# modEEGdigital_v1_1.net
KiCad netlist of a schematic drawn in EAGLE
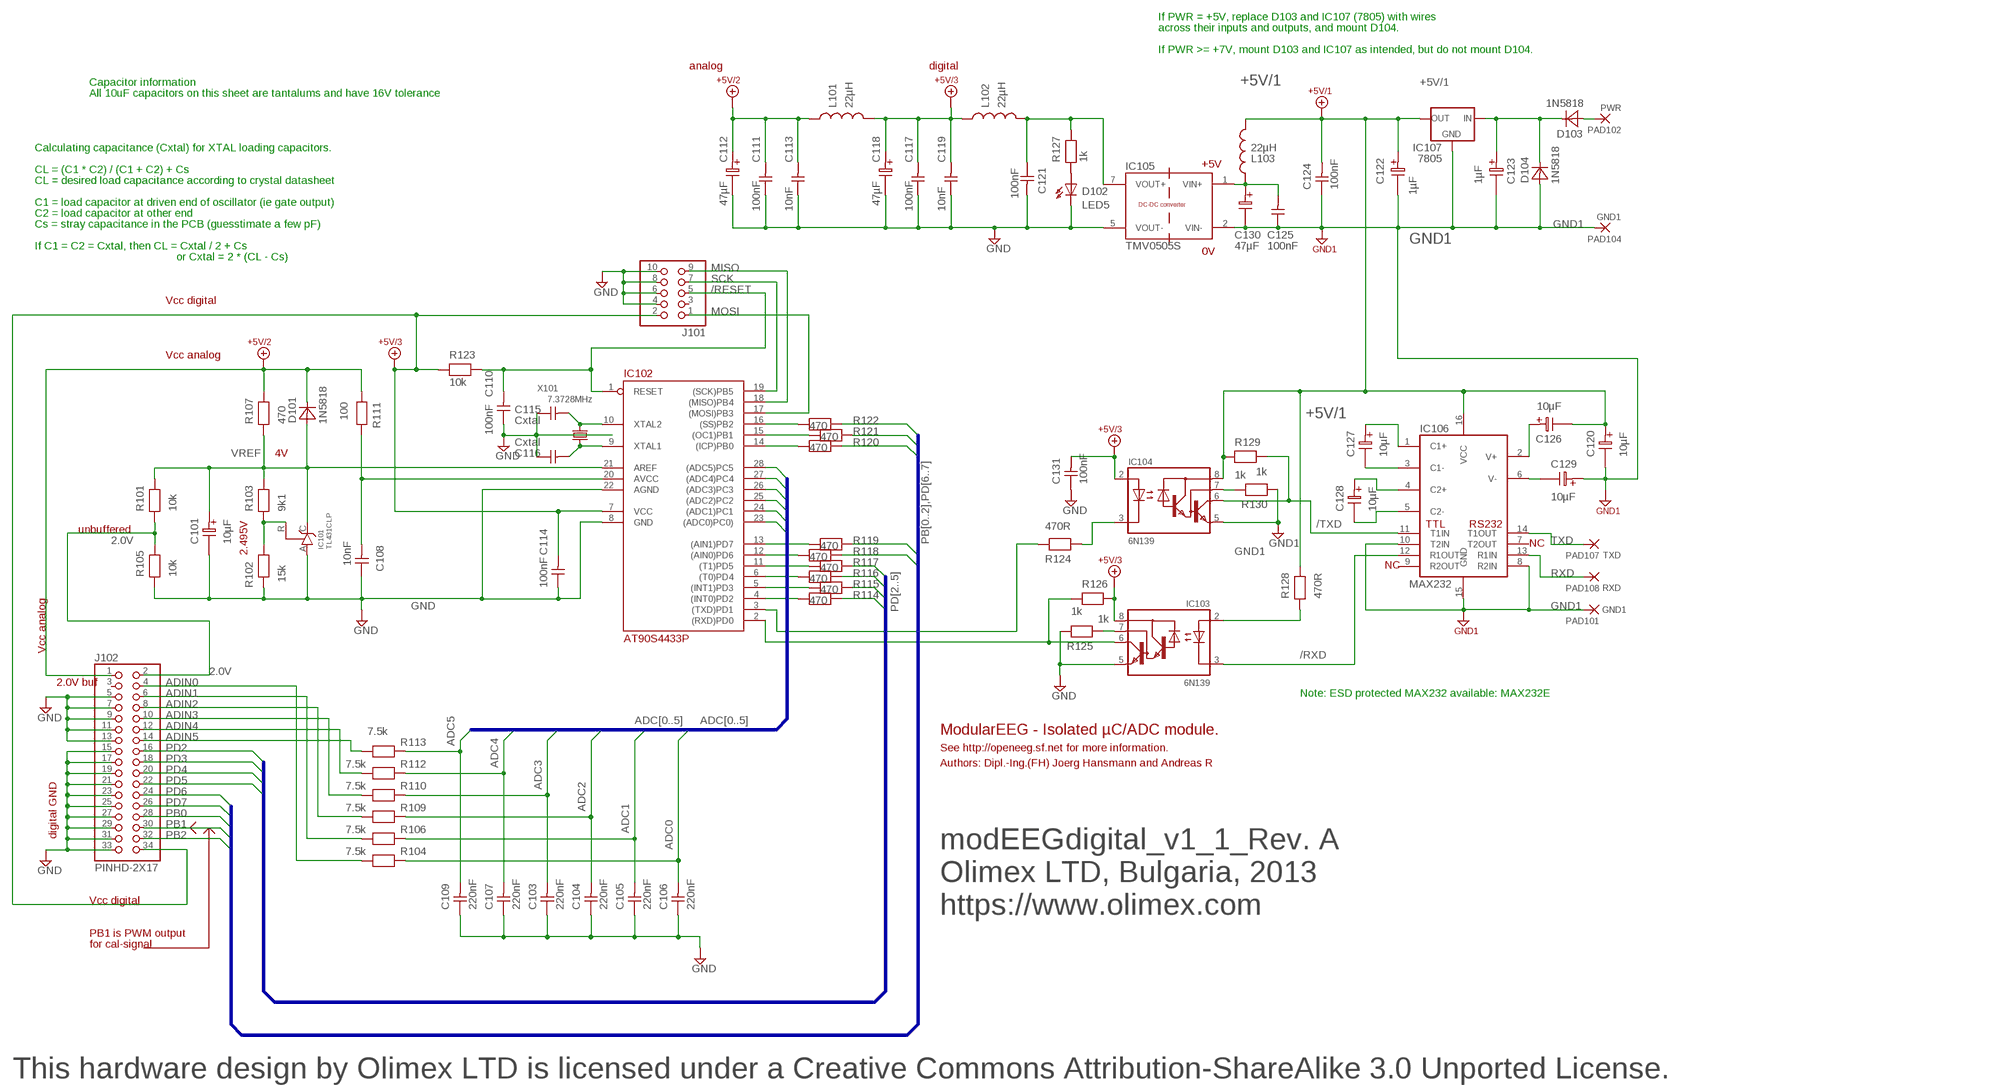
[diagram p0: schematic, sheet 1]

(export (version "E")
  (design (tool "Eeschema 10.0.6"))
  (components
    (comp (ref "C101")
      (value "10µF")
      (footprint "eagle-import:EL25B")
      (libsource (lib "eagle-import") (part "ELC-5"))
    )
    (comp (ref "C103")
      (value "220nF")
      (footprint "eagle-import:C-5")
      (libsource (lib "eagle-import") (part "CAPNP-5"))
    )
    (comp (ref "C104")
      (value "220nF")
      (footprint "eagle-import:C-5")
      (libsource (lib "eagle-import") (part "CAPNP-5"))
    )
    (comp (ref "C105")
      (value "220nF")
      (footprint "eagle-import:C-5")
      (libsource (lib "eagle-import") (part "CAPNP-5"))
    )
    (comp (ref "C106")
      (value "220nF")
      (footprint "eagle-import:C-5")
      (libsource (lib "eagle-import") (part "CAPNP-5"))
    )
    (comp (ref "C107")
      (value "220nF")
      (footprint "eagle-import:C-5")
      (libsource (lib "eagle-import") (part "CAPNP-5"))
    )
    (comp (ref "C108")
      (value "10nF")
      (footprint "eagle-import:C-5")
      (libsource (lib "eagle-import") (part "CAPNP-5"))
    )
    (comp (ref "C109")
      (value "220nF")
      (footprint "eagle-import:C-5")
      (libsource (lib "eagle-import") (part "CAPNP-5"))
    )
    (comp (ref "C110")
      (value "100nF")
      (footprint "eagle-import:C-5")
      (libsource (lib "eagle-import") (part "CAPNP-5"))
    )
    (comp (ref "C111")
      (value "100nF")
      (footprint "eagle-import:C-5")
      (libsource (lib "eagle-import") (part "CAPNP-5"))
    )
    (comp (ref "C112")
      (value "47µF")
      (footprint "eagle-import:EL25B")
      (libsource (lib "eagle-import") (part "ELC-5"))
    )
    (comp (ref "C113")
      (value "10nF")
      (footprint "eagle-import:C-5")
      (libsource (lib "eagle-import") (part "CAPNP-5"))
    )
    (comp (ref "C114")
      (value "100nF")
      (footprint "eagle-import:C-5")
      (libsource (lib "eagle-import") (part "CAPNP-5"))
    )
    (comp (ref "C115")
      (value "Cxtal")
      (footprint "eagle-import:C-5")
      (libsource (lib "eagle-import") (part "CAPNP-5"))
    )
    (comp (ref "C116")
      (value "Cxtal")
      (footprint "eagle-import:C-5")
      (libsource (lib "eagle-import") (part "CAPNP-5"))
    )
    (comp (ref "C117")
      (value "100nF")
      (footprint "eagle-import:C-5")
      (libsource (lib "eagle-import") (part "CAPNP-5"))
    )
    (comp (ref "C118")
      (value "47µF")
      (footprint "eagle-import:EL25B")
      (libsource (lib "eagle-import") (part "ELC-5"))
    )
    (comp (ref "C119")
      (value "10nF")
      (footprint "eagle-import:C-5")
      (libsource (lib "eagle-import") (part "CAPNP-5"))
    )
    (comp (ref "C120")
      (value "10µF")
      (footprint "eagle-import:EL25B")
      (libsource (lib "eagle-import") (part "ELC-5"))
    )
    (comp (ref "C121")
      (value "100nF")
      (footprint "eagle-import:C-5@1")
      (libsource (lib "eagle-import") (part "CAPNP-5@2"))
    )
    (comp (ref "C122")
      (value "1µF")
      (footprint "eagle-import:EL25B")
      (libsource (lib "eagle-import") (part "ELC-2,5"))
    )
    (comp (ref "C123")
      (value "1µF")
      (footprint "eagle-import:EL25B")
      (libsource (lib "eagle-import") (part "ELC-2,5"))
    )
    (comp (ref "C124")
      (value "100nF")
      (footprint "eagle-import:C-5@1")
      (libsource (lib "eagle-import") (part "CAPNP-5@2"))
    )
    (comp (ref "C125")
      (value "100nF")
      (footprint "eagle-import:C-5")
      (libsource (lib "eagle-import") (part "CAPNP-5"))
    )
    (comp (ref "C126")
      (value "10µF")
      (footprint "eagle-import:EL25B")
      (libsource (lib "eagle-import") (part "ELC-5"))
    )
    (comp (ref "C127")
      (value "10µF")
      (footprint "eagle-import:EL25B")
      (libsource (lib "eagle-import") (part "ELC-5"))
    )
    (comp (ref "C128")
      (value "10µF")
      (footprint "eagle-import:EL25B")
      (libsource (lib "eagle-import") (part "ELC-5"))
    )
    (comp (ref "C129")
      (value "10µF")
      (footprint "eagle-import:EL25B")
      (libsource (lib "eagle-import") (part "ELC-5"))
    )
    (comp (ref "C130")
      (value "47µF")
      (footprint "eagle-import:EL25B")
      (libsource (lib "eagle-import") (part "ELC-5"))
    )
    (comp (ref "C131")
      (value "100nF")
      (footprint "eagle-import:C-5")
      (libsource (lib "eagle-import") (part "CAPNP-5"))
    )
    (comp (ref "D101")
      (value "1N5818")
      (footprint "eagle-import:D-10")
      (libsource (lib "eagle-import") (part "DIODE-10"))
    )
    (comp (ref "D102")
      (value "LED5")
      (footprint "eagle-import:LED5")
      (libsource (lib "eagle-import") (part "LED5"))
    )
    (comp (ref "D103")
      (value "1N5818")
      (footprint "eagle-import:D-12,5")
      (libsource (lib "eagle-import") (part "DIODE-12,5"))
    )
    (comp (ref "D104")
      (value "1N5818")
      (footprint "eagle-import:D-12,5")
      (libsource (lib "eagle-import") (part "DIODE-12,5"))
    )
    (comp (ref "IC101")
      (value "TL431CLP")
      (footprint "eagle-import:TO92-CLP")
      (libsource (lib "eagle-import") (part "TL431CLP"))
    )
    (comp (ref "IC102")
      (value "AT90S4433P")
      (footprint "eagle-import:DIL-28_3")
      (libsource (lib "eagle-import") (part "90S4433-P"))
    )
    (comp (ref "IC103")
      (value "6N139")
      (footprint "eagle-import:DIL-08")
      (libsource (lib "eagle-import") (part "HCPL0700"))
    )
    (comp (ref "IC104")
      (value "6N139")
      (footprint "eagle-import:DIL-08")
      (libsource (lib "eagle-import") (part "HCPL0700"))
    )
    (comp (ref "IC105")
      (value "TMV0505S")
      (footprint "eagle-import:TMADCDC")
      (libsource (lib "eagle-import") (part "TMV0505"))
    )
    (comp (ref "IC106")
      (value "MAX232")
      (footprint "eagle-import:DIL-16")
      (libsource (lib "eagle-import") (part "MAX232"))
    )
    (comp (ref "IC107")
      (value "7805")
      (footprint "eagle-import:78XXL_S")
      (libsource (lib "eagle-import") (part "78XXS"))
    )
    (comp (ref "J101")
      (value "PINHD-2X5")
      (footprint "eagle-import:2X05")
      (libsource (lib "eagle-import") (part "PINHD-2X5"))
    )
    (comp (ref "J102")
      (value "PINHD-2X17")
      (footprint "eagle-import:2X17")
      (libsource (lib "eagle-import") (part "PINHD-2X17"))
    )
    (comp (ref "L101")
      (value "22µH")
      (footprint "eagle-import:R-12,5")
      (libsource (lib "eagle-import") (part "L-10"))
    )
    (comp (ref "L102")
      (value "22µH")
      (footprint "eagle-import:R-12,5")
      (libsource (lib "eagle-import") (part "L-10"))
    )
    (comp (ref "L103")
      (value "22µH")
      (footprint "eagle-import:R-12,5")
      (libsource (lib "eagle-import") (part "L-10"))
    )
    (comp (ref "PAD101")
      (value "GND1")
      (footprint "eagle-import:WIREPAD1")
      (libsource (lib "eagle-import") (part "1,6/0,8"))
    )
    (comp (ref "PAD102")
      (value "PWR")
      (footprint "eagle-import:WIREPAD1")
      (libsource (lib "eagle-import") (part "1,6/0,8"))
    )
    (comp (ref "PAD104")
      (value "GND1")
      (footprint "eagle-import:WIREPAD1")
      (libsource (lib "eagle-import") (part "1,6/0,8"))
    )
    (comp (ref "PAD107")
      (value "TXD")
      (footprint "eagle-import:WIREPAD1")
      (libsource (lib "eagle-import") (part "1,6/0,8"))
    )
    (comp (ref "PAD108")
      (value "RXD")
      (footprint "eagle-import:WIREPAD1")
      (libsource (lib "eagle-import") (part "1,6/0,8"))
    )
    (comp (ref "R101")
      (value "10k")
      (footprint "eagle-import:R-10")
      (libsource (lib "eagle-import") (part "RESEU-10"))
    )
    (comp (ref "R102")
      (value "15k")
      (footprint "eagle-import:R-10")
      (libsource (lib "eagle-import") (part "RESEU-10"))
    )
    (comp (ref "R103")
      (value "9k1")
      (footprint "eagle-import:R-10")
      (libsource (lib "eagle-import") (part "RESEU-10"))
    )
    (comp (ref "R104")
      (value "7.5k")
      (footprint "eagle-import:R-10")
      (libsource (lib "eagle-import") (part "RESEU-10"))
    )
    (comp (ref "R105")
      (value "10k")
      (footprint "eagle-import:R-10")
      (libsource (lib "eagle-import") (part "RESEU-10"))
    )
    (comp (ref "R106")
      (value "7.5k")
      (footprint "eagle-import:R-10")
      (libsource (lib "eagle-import") (part "RESEU-10"))
    )
    (comp (ref "R107")
      (value "470")
      (footprint "eagle-import:R-10")
      (libsource (lib "eagle-import") (part "RESEU-10"))
    )
    (comp (ref "R109")
      (value "7.5k")
      (footprint "eagle-import:R-10")
      (libsource (lib "eagle-import") (part "RESEU-10"))
    )
    (comp (ref "R110")
      (value "7.5k")
      (footprint "eagle-import:R-10")
      (libsource (lib "eagle-import") (part "RESEU-10"))
    )
    (comp (ref "R111")
      (value "100")
      (footprint "eagle-import:R-10")
      (libsource (lib "eagle-import") (part "RESEU-10"))
    )
    (comp (ref "R112")
      (value "7.5k")
      (footprint "eagle-import:R-10")
      (libsource (lib "eagle-import") (part "RESEU-10"))
    )
    (comp (ref "R113")
      (value "7.5k")
      (footprint "eagle-import:R-10")
      (libsource (lib "eagle-import") (part "RESEU-10"))
    )
    (comp (ref "R114")
      (value "470")
      (footprint "eagle-import:R-10")
      (libsource (lib "eagle-import") (part "RESEU-10"))
    )
    (comp (ref "R115")
      (value "470")
      (footprint "eagle-import:R-10")
      (libsource (lib "eagle-import") (part "RESEU-10"))
    )
    (comp (ref "R116")
      (value "470")
      (footprint "eagle-import:R-10")
      (libsource (lib "eagle-import") (part "RESEU-10"))
    )
    (comp (ref "R117")
      (value "470")
      (footprint "eagle-import:R-10")
      (libsource (lib "eagle-import") (part "RESEU-10"))
    )
    (comp (ref "R118")
      (value "470")
      (footprint "eagle-import:R-10")
      (libsource (lib "eagle-import") (part "RESEU-10"))
    )
    (comp (ref "R119")
      (value "470")
      (footprint "eagle-import:R-10")
      (libsource (lib "eagle-import") (part "RESEU-10"))
    )
    (comp (ref "R120")
      (value "470")
      (footprint "eagle-import:R-10")
      (libsource (lib "eagle-import") (part "RESEU-10"))
    )
    (comp (ref "R121")
      (value "470")
      (footprint "eagle-import:R-10")
      (libsource (lib "eagle-import") (part "RESEU-10"))
    )
    (comp (ref "R122")
      (value "470")
      (footprint "eagle-import:R-10")
      (libsource (lib "eagle-import") (part "RESEU-10"))
    )
    (comp (ref "R123")
      (value "10k")
      (footprint "eagle-import:R-10")
      (libsource (lib "eagle-import") (part "RESEU-10@2"))
    )
    (comp (ref "R124")
      (value "470R")
      (footprint "eagle-import:R-10")
      (libsource (lib "eagle-import") (part "RESEU-10"))
    )
    (comp (ref "R125")
      (value "1k")
      (footprint "eagle-import:R-10")
      (libsource (lib "eagle-import") (part "RESEU-10"))
    )
    (comp (ref "R126")
      (value "1k")
      (footprint "eagle-import:R-10")
      (libsource (lib "eagle-import") (part "RESEU-10"))
    )
    (comp (ref "R127")
      (value "1k")
      (footprint "eagle-import:R-10")
      (libsource (lib "eagle-import") (part "RESEU-10@2"))
    )
    (comp (ref "R128")
      (value "470R")
      (footprint "eagle-import:R-10")
      (libsource (lib "eagle-import") (part "RESEU-10"))
    )
    (comp (ref "R129")
      (value "1k")
      (footprint "eagle-import:R-10")
      (libsource (lib "eagle-import") (part "RESEU-10"))
    )
    (comp (ref "R130")
      (value "1k")
      (footprint "eagle-import:R-10")
      (libsource (lib "eagle-import") (part "RESEU-10"))
    )
    (comp (ref "X101")
      (value "7.3728MHz")
      (footprint "eagle-import:HC49_S")
      (libsource (lib "eagle-import") (part "HC49/S"))
    )
  )
  (nets
    (net (code "1") (name "+5V{slash}1") (class "Default")
      (node (ref "C120") (pin "1") (pinfunction "1_1") (pintype "passive"))
      (node (ref "C122") (pin "1") (pinfunction "1_1") (pintype "passive"))
      (node (ref "C124") (pin "2") (pinfunction "2_2") (pintype "passive"))
      (node (ref "C126") (pin "2") (pinfunction "2_2") (pintype "passive"))
      (node (ref "IC104") (pin "8") (pinfunction "VCC_8") (pintype "passive"))
      (node (ref "IC106") (pin "16") (pinfunction "VCC_16") (pintype "power_in"))
      (node (ref "IC107") (pin "OUT") (pinfunction "OUT_OUT") (pintype "passive"))
      (node (ref "L103") (pin "2") (pinfunction "2_2") (pintype "passive"))
      (node (ref "R128") (pin "2") (pinfunction "2_2") (pintype "passive"))
      (node (ref "R129") (pin "1") (pinfunction "1_1") (pintype "passive"))
    )
    (net (code "2") (name "+5V{slash}2") (class "Default")
      (node (ref "C111") (pin "2") (pinfunction "2_2") (pintype "passive"))
      (node (ref "C112") (pin "1") (pinfunction "1_1") (pintype "passive"))
      (node (ref "C113") (pin "2") (pinfunction "2_2") (pintype "passive"))
      (node (ref "D101") (pin "2") (pinfunction "K_2") (pintype "passive"))
      (node (ref "J102") (pin "1") (pinfunction "1_1") (pintype "passive"))
      (node (ref "L101") (pin "1") (pinfunction "1_1") (pintype "passive"))
      (node (ref "R107") (pin "2") (pinfunction "2_2") (pintype "passive"))
      (node (ref "R111") (pin "1") (pinfunction "1_1") (pintype "passive"))
    )
    (net (code "3") (name "+5V{slash}3") (class "Default")
      (node (ref "C114") (pin "2") (pinfunction "2_2") (pintype "passive"))
      (node (ref "C117") (pin "2") (pinfunction "2_2") (pintype "passive"))
      (node (ref "C118") (pin "1") (pinfunction "1_1") (pintype "passive"))
      (node (ref "C119") (pin "2") (pinfunction "2_2") (pintype "passive"))
      (node (ref "C131") (pin "2") (pinfunction "2_2") (pintype "passive"))
      (node (ref "IC102") (pin "7") (pinfunction "VCC_7") (pintype "power_in"))
      (node (ref "IC103") (pin "8") (pinfunction "VCC_8") (pintype "passive"))
      (node (ref "IC104") (pin "2") (pinfunction "A_2") (pintype "passive"))
      (node (ref "J101") (pin "2") (pinfunction "2_2") (pintype "passive"))
      (node (ref "J102") (pin "34") (pinfunction "34_34") (pintype "passive"))
      (node (ref "L101") (pin "2") (pinfunction "2_2") (pintype "passive"))
      (node (ref "L102") (pin "1") (pinfunction "1_1") (pintype "passive"))
      (node (ref "R123") (pin "1") (pinfunction "1_1") (pintype "passive"))
      (node (ref "R126") (pin "2") (pinfunction "2_2") (pintype "passive"))
    )
    (net (code "4") (name "/2.0V") (class "Default")
      (node (ref "J102") (pin "2") (pinfunction "2_2") (pintype "passive"))
      (node (ref "R101") (pin "1") (pinfunction "1_1") (pintype "passive"))
      (node (ref "R105") (pin "2") (pinfunction "2_2") (pintype "passive"))
    )
    (net (code "5") (name "/ADC0") (class "Default")
      (node (ref "C106") (pin "2") (pinfunction "2_2") (pintype "passive"))
      (node (ref "IC102") (pin "23") (pinfunction "(ADC0)PC0)_23") (pintype "bidirectional"))
      (node (ref "R104") (pin "2") (pinfunction "2_2") (pintype "passive"))
    )
    (net (code "6") (name "/ADC1") (class "Default")
      (node (ref "C105") (pin "2") (pinfunction "2_2") (pintype "passive"))
      (node (ref "IC102") (pin "24") (pinfunction "(ADC1)PC1_24") (pintype "bidirectional"))
      (node (ref "R106") (pin "2") (pinfunction "2_2") (pintype "passive"))
    )
    (net (code "7") (name "/ADC2") (class "Default")
      (node (ref "C104") (pin "2") (pinfunction "2_2") (pintype "passive"))
      (node (ref "IC102") (pin "25") (pinfunction "(ADC2)PC2_25") (pintype "bidirectional"))
      (node (ref "R109") (pin "2") (pinfunction "2_2") (pintype "passive"))
    )
    (net (code "8") (name "/ADC3") (class "Default")
      (node (ref "C103") (pin "2") (pinfunction "2_2") (pintype "passive"))
      (node (ref "IC102") (pin "26") (pinfunction "(ADC3)PC3_26") (pintype "bidirectional"))
      (node (ref "R110") (pin "2") (pinfunction "2_2") (pintype "passive"))
    )
    (net (code "9") (name "/ADC4") (class "Default")
      (node (ref "C107") (pin "2") (pinfunction "2_2") (pintype "passive"))
      (node (ref "IC102") (pin "27") (pinfunction "(ADC4)PC4_27") (pintype "bidirectional"))
      (node (ref "R112") (pin "2") (pinfunction "2_2") (pintype "passive"))
    )
    (net (code "10") (name "/ADC5") (class "Default")
      (node (ref "C109") (pin "2") (pinfunction "2_2") (pintype "passive"))
      (node (ref "IC102") (pin "28") (pinfunction "(ADC5)PC5_28") (pintype "bidirectional"))
      (node (ref "R113") (pin "2") (pinfunction "2_2") (pintype "passive"))
    )
    (net (code "12") (name "/ADIN0") (class "Default")
      (node (ref "J102") (pin "4") (pinfunction "4_4") (pintype "passive"))
      (node (ref "R104") (pin "1") (pinfunction "1_1") (pintype "passive"))
    )
    (net (code "13") (name "/ADIN1") (class "Default")
      (node (ref "J102") (pin "6") (pinfunction "6_6") (pintype "passive"))
      (node (ref "R106") (pin "1") (pinfunction "1_1") (pintype "passive"))
    )
    (net (code "14") (name "/ADIN2") (class "Default")
      (node (ref "J102") (pin "8") (pinfunction "8_8") (pintype "passive"))
      (node (ref "R109") (pin "1") (pinfunction "1_1") (pintype "passive"))
    )
    (net (code "15") (name "/ADIN3") (class "Default")
      (node (ref "J102") (pin "10") (pinfunction "10_10") (pintype "passive"))
      (node (ref "R110") (pin "1") (pinfunction "1_1") (pintype "passive"))
    )
    (net (code "16") (name "/ADIN4") (class "Default")
      (node (ref "J102") (pin "12") (pinfunction "12_12") (pintype "passive"))
      (node (ref "R112") (pin "1") (pinfunction "1_1") (pintype "passive"))
    )
    (net (code "17") (name "/ADIN5") (class "Default")
      (node (ref "J102") (pin "14") (pinfunction "14_14") (pintype "passive"))
      (node (ref "R113") (pin "1") (pinfunction "1_1") (pintype "passive"))
    )
    (net (code "18") (name "/MISO") (class "Default")
      (node (ref "IC102") (pin "18") (pinfunction "(MISO)PB4_18") (pintype "bidirectional"))
      (node (ref "J101") (pin "9") (pinfunction "9_9") (pintype "passive"))
    )
    (net (code "19") (name "/MOSI") (class "Default")
      (node (ref "IC102") (pin "17") (pinfunction "(MOSI)PB3_17") (pintype "bidirectional"))
      (node (ref "J101") (pin "1") (pinfunction "1_1") (pintype "passive"))
    )
    (net (code "20") (name "/PB0") (class "Default")
      (node (ref "J102") (pin "28") (pinfunction "28_28") (pintype "passive"))
      (node (ref "R120") (pin "2") (pinfunction "2_2") (pintype "passive"))
    )
    (net (code "21") (name "/PB1") (class "Default")
      (node (ref "J102") (pin "30") (pinfunction "30_30") (pintype "passive"))
      (node (ref "R121") (pin "2") (pinfunction "2_2") (pintype "passive"))
    )
    (net (code "22") (name "/PB2") (class "Default")
      (node (ref "J102") (pin "32") (pinfunction "32_32") (pintype "passive"))
      (node (ref "R122") (pin "2") (pinfunction "2_2") (pintype "passive"))
    )
    (net (code "23") (name "/PD2") (class "Default")
      (node (ref "J102") (pin "16") (pinfunction "16_16") (pintype "passive"))
      (node (ref "R114") (pin "2") (pinfunction "2_2") (pintype "passive"))
    )
    (net (code "24") (name "/PD3") (class "Default")
      (node (ref "J102") (pin "18") (pinfunction "18_18") (pintype "passive"))
      (node (ref "R115") (pin "2") (pinfunction "2_2") (pintype "passive"))
    )
    (net (code "25") (name "/PD4") (class "Default")
      (node (ref "J102") (pin "20") (pinfunction "20_20") (pintype "passive"))
      (node (ref "R116") (pin "2") (pinfunction "2_2") (pintype "passive"))
    )
    (net (code "26") (name "/PD5") (class "Default")
      (node (ref "J102") (pin "22") (pinfunction "22_22") (pintype "passive"))
      (node (ref "R117") (pin "2") (pinfunction "2_2") (pintype "passive"))
    )
    (net (code "27") (name "/PD6") (class "Default")
      (node (ref "J102") (pin "24") (pinfunction "24_24") (pintype "passive"))
      (node (ref "R118") (pin "2") (pinfunction "2_2") (pintype "passive"))
    )
    (net (code "28") (name "/PD7") (class "Default")
      (node (ref "J102") (pin "26") (pinfunction "26_26") (pintype "passive"))
      (node (ref "R119") (pin "2") (pinfunction "2_2") (pintype "passive"))
    )
    (net (code "29") (name "/RXD") (class "Default")
      (node (ref "IC106") (pin "13") (pinfunction "R1IN_13") (pintype "input"))
      (node (ref "PAD108") (pin "1") (pinfunction "P_1") (pintype "passive"))
    )
    (net (code "30") (name "/SCK") (class "Default")
      (node (ref "IC102") (pin "19") (pinfunction "(SCK)PB5_19") (pintype "bidirectional"))
      (node (ref "J101") (pin "7") (pinfunction "7_7") (pintype "passive"))
    )
    (net (code "31") (name "/TXD") (class "Default")
      (node (ref "IC106") (pin "14") (pinfunction "T1OUT_14") (pintype "output"))
      (node (ref "PAD107") (pin "1") (pinfunction "P_1") (pintype "passive"))
    )
    (net (code "32") (name "/VREF") (class "Default")
      (node (ref "C101") (pin "1") (pinfunction "1_1") (pintype "passive"))
      (node (ref "D101") (pin "1") (pinfunction "A_1") (pintype "passive"))
      (node (ref "IC101") (pin "C") (pinfunction "C_C") (pintype "passive"))
      (node (ref "IC102") (pin "21") (pinfunction "AREF_21") (pintype "power_in"))
      (node (ref "R101") (pin "2") (pinfunction "2_2") (pintype "passive"))
      (node (ref "R103") (pin "2") (pinfunction "2_2") (pintype "passive"))
      (node (ref "R107") (pin "1") (pinfunction "1_1") (pintype "passive"))
    )
    (net (code "34") (name "/{slash}RESET") (class "Default")
      (node (ref "C110") (pin "2") (pinfunction "2_2") (pintype "passive"))
      (node (ref "IC102") (pin "1") (pinfunction "RESET_1") (pintype "input"))
      (node (ref "J101") (pin "5") (pinfunction "5_5") (pintype "passive"))
      (node (ref "R123") (pin "2") (pinfunction "2_2") (pintype "passive"))
    )
    (net (code "35") (name "/{slash}RXD") (class "Default")
      (node (ref "IC103") (pin "3") (pinfunction "K_3") (pintype "passive"))
      (node (ref "IC106") (pin "12") (pinfunction "R1OUT_12") (pintype "output"))
    )
    (net (code "36") (name "/{slash}TXD") (class "Default")
      (node (ref "IC104") (pin "6") (pinfunction "VO_6") (pintype "passive"))
      (node (ref "IC106") (pin "11") (pinfunction "T1IN_11") (pintype "input"))
      (node (ref "R129") (pin "2") (pinfunction "2_2") (pintype "passive"))
    )
    (net (code "37") (name "GND") (class "Default")
      (node (ref "C101") (pin "2") (pinfunction "2_2") (pintype "passive"))
      (node (ref "C103") (pin "1") (pinfunction "1_1") (pintype "passive"))
      (node (ref "C104") (pin "1") (pinfunction "1_1") (pintype "passive"))
      (node (ref "C105") (pin "1") (pinfunction "1_1") (pintype "passive"))
      (node (ref "C106") (pin "1") (pinfunction "1_1") (pintype "passive"))
      (node (ref "C107") (pin "1") (pinfunction "1_1") (pintype "passive"))
      (node (ref "C108") (pin "1") (pinfunction "1_1") (pintype "passive"))
      (node (ref "C109") (pin "1") (pinfunction "1_1") (pintype "passive"))
      (node (ref "C110") (pin "1") (pinfunction "1_1") (pintype "passive"))
      (node (ref "C111") (pin "1") (pinfunction "1_1") (pintype "passive"))
      (node (ref "C112") (pin "2") (pinfunction "2_2") (pintype "passive"))
      (node (ref "C113") (pin "1") (pinfunction "1_1") (pintype "passive"))
      (node (ref "C114") (pin "1") (pinfunction "1_1") (pintype "passive"))
      (node (ref "C115") (pin "1") (pinfunction "1_1") (pintype "passive"))
      (node (ref "C116") (pin "1") (pinfunction "1_1") (pintype "passive"))
      (node (ref "C117") (pin "1") (pinfunction "1_1") (pintype "passive"))
      (node (ref "C118") (pin "2") (pinfunction "2_2") (pintype "passive"))
      (node (ref "C119") (pin "1") (pinfunction "1_1") (pintype "passive"))
      (node (ref "C121") (pin "2") (pinfunction "2_2") (pintype "passive"))
      (node (ref "C131") (pin "1") (pinfunction "1_1") (pintype "passive"))
      (node (ref "D102") (pin "K") (pinfunction "K_K") (pintype "passive"))
      (node (ref "IC101") (pin "A") (pinfunction "A_A") (pintype "passive"))
      (node (ref "IC102") (pin "22") (pinfunction "AGND_22") (pintype "power_in"))
      (node (ref "IC102") (pin "8") (pinfunction "GND_8") (pintype "power_in"))
      (node (ref "IC103") (pin "5") (pinfunction "GND_5") (pintype "passive"))
      (node (ref "IC105") (pin "5") (pinfunction "VOUT-_5") (pintype "power_in"))
      (node (ref "J101") (pin "10") (pinfunction "10_10") (pintype "passive"))
      (node (ref "J101") (pin "4") (pinfunction "4_4") (pintype "passive"))
      (node (ref "J101") (pin "6") (pinfunction "6_6") (pintype "passive"))
      (node (ref "J101") (pin "8") (pinfunction "8_8") (pintype "passive"))
      (node (ref "J102") (pin "11") (pinfunction "11_11") (pintype "passive"))
      (node (ref "J102") (pin "13") (pinfunction "13_13") (pintype "passive"))
      (node (ref "J102") (pin "15") (pinfunction "15_15") (pintype "passive"))
      (node (ref "J102") (pin "17") (pinfunction "17_17") (pintype "passive"))
      (node (ref "J102") (pin "19") (pinfunction "19_19") (pintype "passive"))
      (node (ref "J102") (pin "21") (pinfunction "21_21") (pintype "passive"))
      (node (ref "J102") (pin "23") (pinfunction "23_23") (pintype "passive"))
      (node (ref "J102") (pin "25") (pinfunction "25_25") (pintype "passive"))
      (node (ref "J102") (pin "27") (pinfunction "27_27") (pintype "passive"))
      (node (ref "J102") (pin "29") (pinfunction "29_29") (pintype "passive"))
      (node (ref "J102") (pin "31") (pinfunction "31_31") (pintype "passive"))
      (node (ref "J102") (pin "33") (pinfunction "33_33") (pintype "passive"))
      (node (ref "J102") (pin "5") (pinfunction "5_5") (pintype "passive"))
      (node (ref "J102") (pin "7") (pinfunction "7_7") (pintype "passive"))
      (node (ref "J102") (pin "9") (pinfunction "9_9") (pintype "passive"))
      (node (ref "R102") (pin "1") (pinfunction "1_1") (pintype "passive"))
      (node (ref "R105") (pin "1") (pinfunction "1_1") (pintype "passive"))
      (node (ref "R125") (pin "2") (pinfunction "2_2") (pintype "passive"))
    )
    (net (code "38") (name "GND1") (class "Default")
      (node (ref "C120") (pin "2") (pinfunction "2_2") (pintype "passive"))
      (node (ref "C122") (pin "2") (pinfunction "2_2") (pintype "passive"))
      (node (ref "C123") (pin "2") (pinfunction "2_2") (pintype "passive"))
      (node (ref "C124") (pin "1") (pinfunction "1_1") (pintype "passive"))
      (node (ref "C125") (pin "1") (pinfunction "1_1") (pintype "passive"))
      (node (ref "C129") (pin "1") (pinfunction "1_1") (pintype "passive"))
      (node (ref "C130") (pin "2") (pinfunction "2_2") (pintype "passive"))
      (node (ref "D104") (pin "1") (pinfunction "A_1") (pintype "passive"))
      (node (ref "IC104") (pin "5") (pinfunction "GND_5") (pintype "passive"))
      (node (ref "IC105") (pin "2") (pinfunction "VIN-_2") (pintype "power_in"))
      (node (ref "IC106") (pin "10") (pinfunction "T2IN_10") (pintype "input"))
      (node (ref "IC106") (pin "15") (pinfunction "GND_15") (pintype "power_in"))
      (node (ref "IC106") (pin "8") (pinfunction "R2IN_8") (pintype "input"))
      (node (ref "IC107") (pin "GND") (pinfunction "GND_GND") (pintype "input"))
      (node (ref "PAD101") (pin "1") (pinfunction "P_1") (pintype "passive"))
      (node (ref "PAD104") (pin "1") (pinfunction "P_1") (pintype "passive"))
      (node (ref "R130") (pin "1") (pinfunction "1_1") (pintype "passive"))
    )
    (net (code "39") (name "Net-(D102-PadA)") (class "Default")
      (node (ref "D102") (pin "A") (pinfunction "A_A") (pintype "passive"))
      (node (ref "R127") (pin "1") (pinfunction "1_1") (pintype "passive"))
    )
    (net (code "40") (name "Net-(D103-A)") (class "Default")
      (node (ref "D103") (pin "1") (pinfunction "A_1") (pintype "passive"))
      (node (ref "PAD102") (pin "1") (pinfunction "P_1") (pintype "passive"))
    )
    (net (code "41") (name "Net-(D103-K)") (class "Default")
      (node (ref "C123") (pin "1") (pinfunction "1_1") (pintype "passive"))
      (node (ref "D103") (pin "2") (pinfunction "K_2") (pintype "passive"))
      (node (ref "D104") (pin "2") (pinfunction "K_2") (pintype "passive"))
      (node (ref "IC107") (pin "IN") (pinfunction "IN_IN") (pintype "input"))
    )
    (net (code "42") (name "Net-(IC101-PadR)") (class "Default")
      (node (ref "IC101") (pin "R") (pinfunction "R_R") (pintype "passive"))
      (node (ref "R102") (pin "2") (pinfunction "2_2") (pintype "passive"))
      (node (ref "R103") (pin "1") (pinfunction "1_1") (pintype "passive"))
    )
    (net (code "43") (name "Net-(IC102-(AIN0)PD6)") (class "Default")
      (node (ref "IC102") (pin "12") (pinfunction "(AIN0)PD6_12") (pintype "bidirectional"))
      (node (ref "R118") (pin "1") (pinfunction "1_1") (pintype "passive"))
    )
    (net (code "44") (name "Net-(IC102-(AIN1)PD7)") (class "Default")
      (node (ref "IC102") (pin "13") (pinfunction "(AIN1)PD7_13") (pintype "bidirectional"))
      (node (ref "R119") (pin "1") (pinfunction "1_1") (pintype "passive"))
    )
    (net (code "45") (name "Net-(IC102-(ICP)PB0)") (class "Default")
      (node (ref "IC102") (pin "14") (pinfunction "(ICP)PB0_14") (pintype "bidirectional"))
      (node (ref "R120") (pin "1") (pinfunction "1_1") (pintype "passive"))
    )
    (net (code "46") (name "Net-(IC102-(INT0)PD2)") (class "Default")
      (node (ref "IC102") (pin "4") (pinfunction "(INT0)PD2_4") (pintype "bidirectional"))
      (node (ref "R114") (pin "1") (pinfunction "1_1") (pintype "passive"))
    )
    (net (code "47") (name "Net-(IC102-(INT1)PD3)") (class "Default")
      (node (ref "IC102") (pin "5") (pinfunction "(INT1)PD3_5") (pintype "bidirectional"))
      (node (ref "R115") (pin "1") (pinfunction "1_1") (pintype "passive"))
    )
    (net (code "48") (name "Net-(IC102-(OC1)PB1)") (class "Default")
      (node (ref "IC102") (pin "15") (pinfunction "(OC1)PB1_15") (pintype "bidirectional"))
      (node (ref "R121") (pin "1") (pinfunction "1_1") (pintype "passive"))
    )
    (net (code "49") (name "Net-(IC102-(RXD)PD0)") (class "Default")
      (node (ref "IC102") (pin "2") (pinfunction "(RXD)PD0_2") (pintype "bidirectional"))
      (node (ref "IC103") (pin "6") (pinfunction "VO_6") (pintype "passive"))
      (node (ref "R126") (pin "1") (pinfunction "1_1") (pintype "passive"))
    )
    (net (code "50") (name "Net-(IC102-(SS)PB2)") (class "Default")
      (node (ref "IC102") (pin "16") (pinfunction "(SS)PB2_16") (pintype "bidirectional"))
      (node (ref "R122") (pin "1") (pinfunction "1_1") (pintype "passive"))
    )
    (net (code "51") (name "Net-(IC102-(T0)PD4)") (class "Default")
      (node (ref "IC102") (pin "6") (pinfunction "(T0)PD4_6") (pintype "bidirectional"))
      (node (ref "R116") (pin "1") (pinfunction "1_1") (pintype "passive"))
    )
    (net (code "52") (name "Net-(IC102-(T1)PD5)") (class "Default")
      (node (ref "IC102") (pin "11") (pinfunction "(T1)PD5_11") (pintype "bidirectional"))
      (node (ref "R117") (pin "1") (pinfunction "1_1") (pintype "passive"))
    )
    (net (code "53") (name "Net-(IC102-(TXD)PD1)") (class "Default")
      (node (ref "IC102") (pin "3") (pinfunction "(TXD)PD1_3") (pintype "bidirectional"))
      (node (ref "R124") (pin "2") (pinfunction "2_2") (pintype "passive"))
    )
    (net (code "54") (name "Net-(IC102-AVCC)") (class "Default")
      (node (ref "C108") (pin "2") (pinfunction "2_2") (pintype "passive"))
      (node (ref "IC102") (pin "20") (pinfunction "AVCC_20") (pintype "power_in"))
      (node (ref "R111") (pin "2") (pinfunction "2_2") (pintype "passive"))
    )
    (net (code "55") (name "Net-(IC102-XTAL1)") (class "Default")
      (node (ref "C116") (pin "2") (pinfunction "2_2") (pintype "passive"))
      (node (ref "IC102") (pin "9") (pinfunction "XTAL1_9") (pintype "bidirectional"))
      (node (ref "X101") (pin "1") (pinfunction "1_1") (pintype "passive"))
    )
    (net (code "56") (name "Net-(IC102-XTAL2)") (class "Default")
      (node (ref "C115") (pin "2") (pinfunction "2_2") (pintype "passive"))
      (node (ref "IC102") (pin "10") (pinfunction "XTAL2_10") (pintype "bidirectional"))
      (node (ref "X101") (pin "2") (pinfunction "2_2") (pintype "passive"))
    )
    (net (code "57") (name "Net-(IC103-A)") (class "Default")
      (node (ref "IC103") (pin "2") (pinfunction "A_2") (pintype "passive"))
      (node (ref "R128") (pin "1") (pinfunction "1_1") (pintype "passive"))
    )
    (net (code "58") (name "Net-(IC103-VB)") (class "Default")
      (node (ref "IC103") (pin "7") (pinfunction "VB_7") (pintype "passive"))
      (node (ref "R125") (pin "1") (pinfunction "1_1") (pintype "passive"))
    )
    (net (code "59") (name "Net-(IC104-K)") (class "Default")
      (node (ref "IC104") (pin "3") (pinfunction "K_3") (pintype "passive"))
      (node (ref "R124") (pin "1") (pinfunction "1_1") (pintype "passive"))
    )
    (net (code "60") (name "Net-(IC104-VB)") (class "Default")
      (node (ref "IC104") (pin "7") (pinfunction "VB_7") (pintype "passive"))
      (node (ref "R130") (pin "2") (pinfunction "2_2") (pintype "passive"))
    )
    (net (code "61") (name "Net-(IC105-VIN+)") (class "Default")
      (node (ref "C125") (pin "2") (pinfunction "2_2") (pintype "passive"))
      (node (ref "C130") (pin "1") (pinfunction "1_1") (pintype "passive"))
      (node (ref "IC105") (pin "1") (pinfunction "VIN+_1") (pintype "power_in"))
      (node (ref "L103") (pin "1") (pinfunction "1_1") (pintype "passive"))
    )
    (net (code "62") (name "Net-(IC105-VOUT+)") (class "Default")
      (node (ref "C121") (pin "1") (pinfunction "1_1") (pintype "passive"))
      (node (ref "IC105") (pin "7") (pinfunction "VOUT+_7") (pintype "power_in"))
      (node (ref "L102") (pin "2") (pinfunction "2_2") (pintype "passive"))
      (node (ref "R127") (pin "2") (pinfunction "2_2") (pintype "passive"))
    )
    (net (code "63") (name "Net-(IC106A-C1+)") (class "Default")
      (node (ref "C127") (pin "1") (pinfunction "1_1") (pintype "passive"))
      (node (ref "IC106") (pin "1") (pinfunction "C1+_1") (pintype "bidirectional"))
    )
    (net (code "64") (name "Net-(IC106A-C1-)") (class "Default")
      (node (ref "C127") (pin "2") (pinfunction "2_2") (pintype "passive"))
      (node (ref "IC106") (pin "3") (pinfunction "C1-_3") (pintype "bidirectional"))
    )
    (net (code "65") (name "Net-(IC106A-C2+)") (class "Default")
      (node (ref "C128") (pin "1") (pinfunction "1_1") (pintype "passive"))
      (node (ref "IC106") (pin "4") (pinfunction "C2+_4") (pintype "bidirectional"))
    )
    (net (code "66") (name "Net-(IC106A-C2-)") (class "Default")
      (node (ref "C128") (pin "2") (pinfunction "2_2") (pintype "passive"))
      (node (ref "IC106") (pin "5") (pinfunction "C2-_5") (pintype "bidirectional"))
    )
    (net (code "67") (name "Net-(IC106A-V+)") (class "Default")
      (node (ref "C126") (pin "1") (pinfunction "1_1") (pintype "passive"))
      (node (ref "IC106") (pin "2") (pinfunction "V+_2") (pintype "bidirectional"))
    )
    (net (code "68") (name "Net-(IC106A-V-)") (class "Default")
      (node (ref "C129") (pin "2") (pinfunction "2_2") (pintype "passive"))
      (node (ref "IC106") (pin "6") (pinfunction "V-_6") (pintype "bidirectional"))
    )
    (net (code "69") (name "unconnected-(IC106A-R2OUT-Pad9)") (class "Default")
      (node (ref "IC106") (pin "9") (pinfunction "R2OUT_9") (pintype "output"))
    )
    (net (code "70") (name "unconnected-(IC106A-T2OUT-Pad7)") (class "Default")
      (node (ref "IC106") (pin "7") (pinfunction "T2OUT_7") (pintype "output"))
    )
    (net (code "71") (name "unconnected-(J101-Pad3)") (class "Default")
      (node (ref "J101") (pin "3") (pinfunction "3_3") (pintype "passive"))
    )
    (net (code "72") (name "unconnected-(J102-Pad3)") (class "Default")
      (node (ref "J102") (pin "3") (pinfunction "3_3") (pintype "passive"))
    )
  )
)
